# schematic.net
KiCad netlist of a schematic drawn in EAGLE
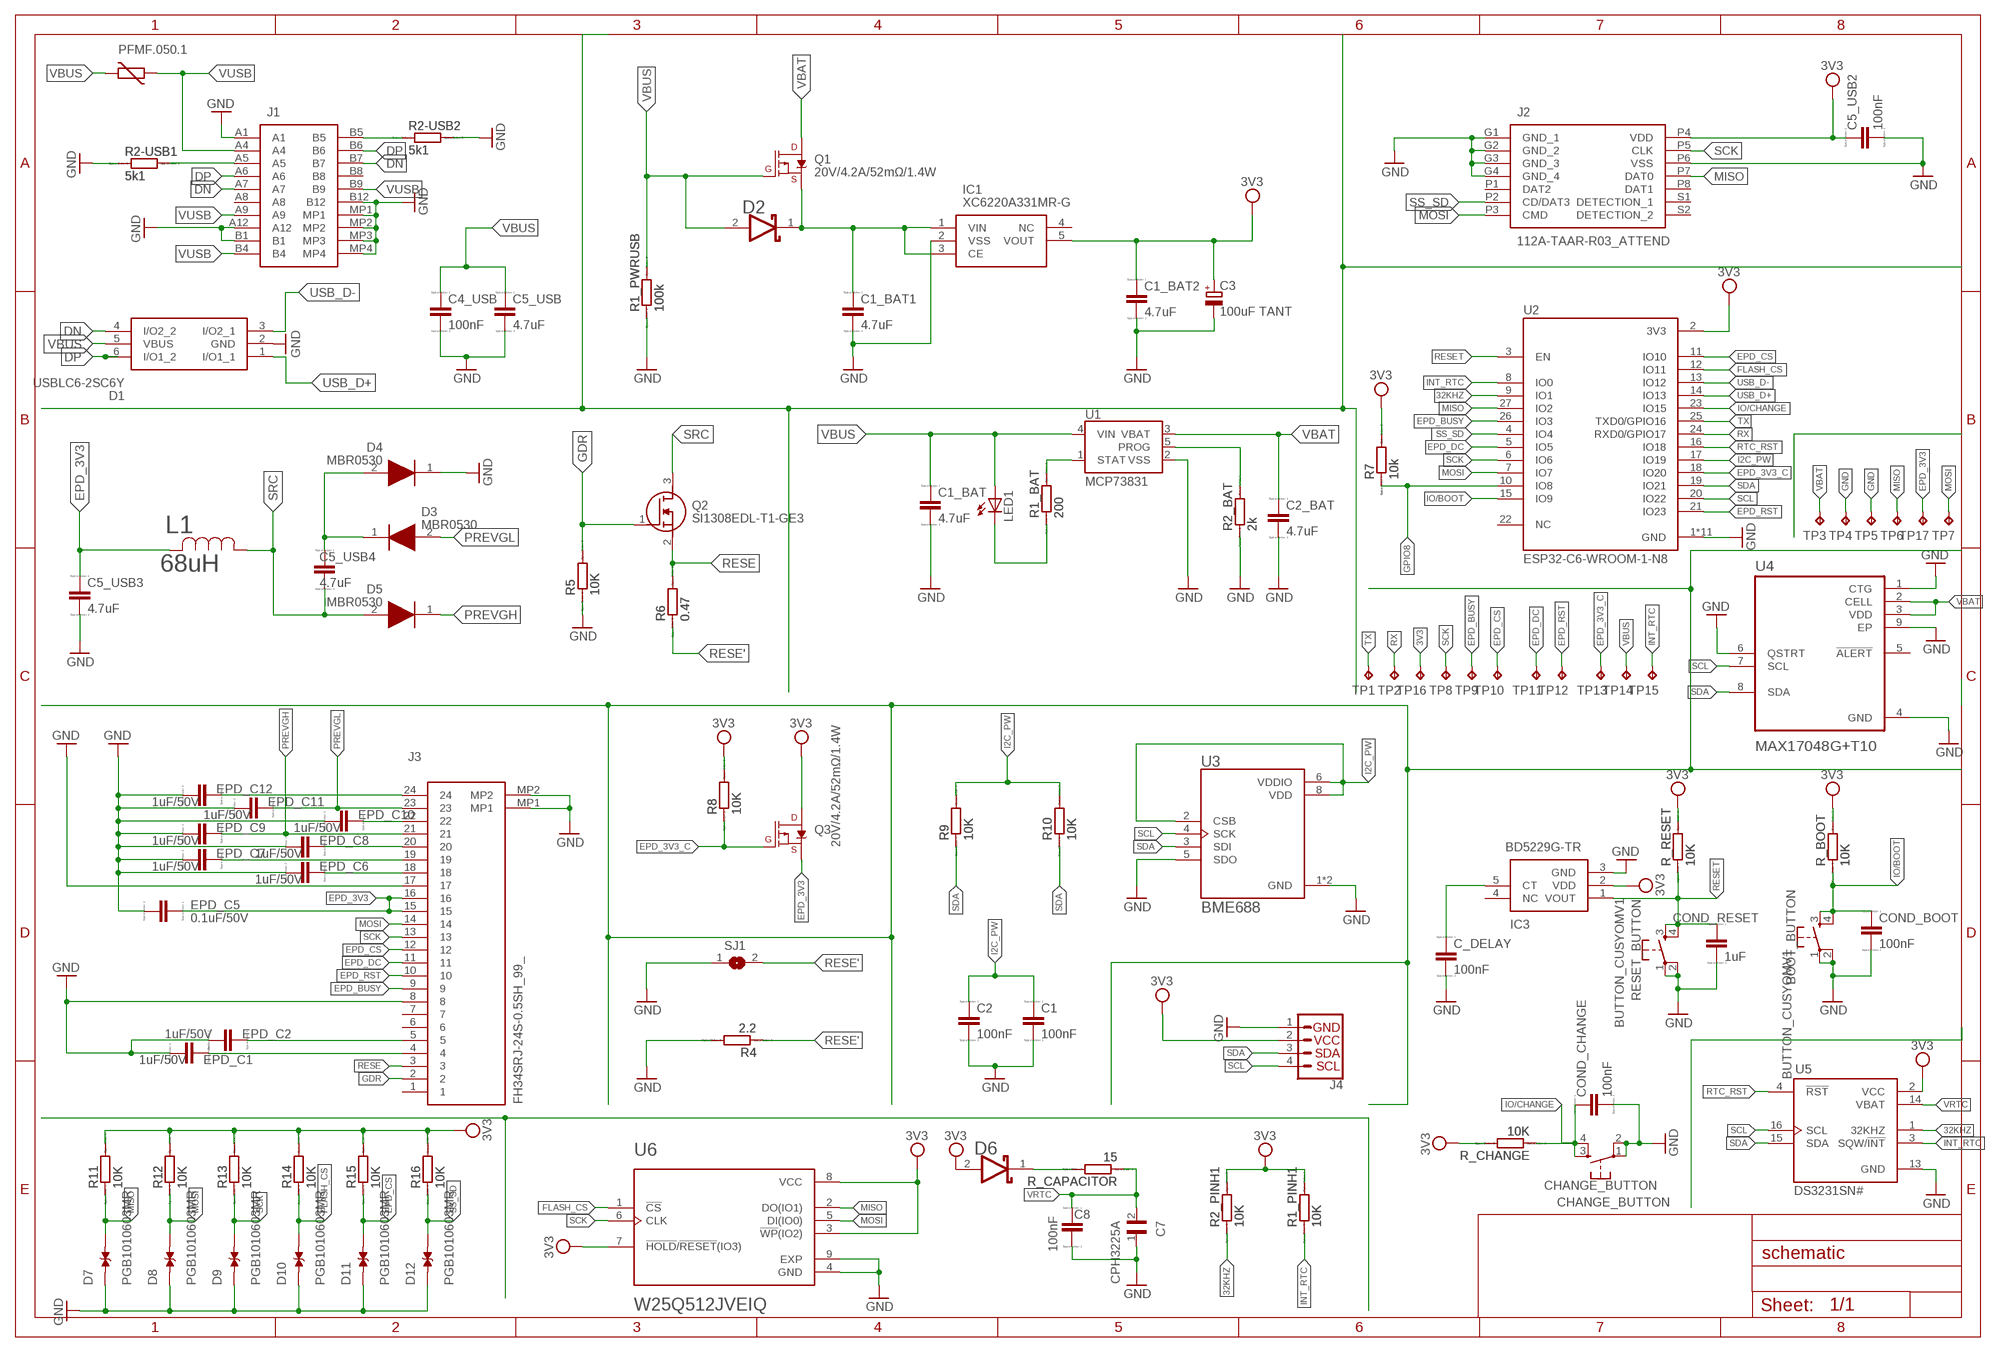
[diagram p0: schematic, sheet 1]

(export (version "E")
  (design (tool "Eeschema 10.0.6"))
  (components
    (comp (ref "BOOT_BUTTON")
      (value "BUTTON_CUSYOMV1")
      (footprint "eagle-import:MYBUTTON")
      (libsource (lib "eagle-import") (part "BUTTON_CUSYOMV1"))
    )
    (comp (ref "C1")
      (value "100nF")
      (footprint "eagle-import:ESP32_WROVER_EAGLE-LTSPICE_C0402")
      (libsource (lib "eagle-import") (part "ESP32_WROVER_EAGLE-LTSPICE_CC0402"))
    )
    (comp (ref "C1_BAT")
      (value "4.7uF")
      (footprint "eagle-import:ESP32_WROVER_EAGLE-LTSPICE_C0402")
      (libsource (lib "eagle-import") (part "ESP32_WROVER_EAGLE-LTSPICE_CC0402"))
    )
    (comp (ref "C1_BAT1")
      (value "4.7uF")
      (footprint "eagle-import:ESP32_WROVER_EAGLE-LTSPICE_C0402")
      (libsource (lib "eagle-import") (part "ESP32_WROVER_EAGLE-LTSPICE_CC0402"))
    )
    (comp (ref "C1_BAT2")
      (value "4.7uF")
      (footprint "eagle-import:ESP32_WROVER_EAGLE-LTSPICE_C0402")
      (libsource (lib "eagle-import") (part "ESP32_WROVER_EAGLE-LTSPICE_CC0402"))
    )
    (comp (ref "C2")
      (value "100nF")
      (footprint "eagle-import:ESP32_WROVER_EAGLE-LTSPICE_C0402")
      (libsource (lib "eagle-import") (part "ESP32_WROVER_EAGLE-LTSPICE_CC0402"))
    )
    (comp (ref "C2_BAT")
      (value "4.7uF")
      (footprint "eagle-import:ESP32_WROVER_EAGLE-LTSPICE_C0402")
      (libsource (lib "eagle-import") (part "ESP32_WROVER_EAGLE-LTSPICE_CC0402"))
    )
    (comp (ref "C3")
      (value "100uF TANT")
      (footprint "eagle-import:RCL_CT3528")
      (libsource (lib "eagle-import") (part "RCL_CPOL-EUCT3528"))
    )
    (comp (ref "C4_USB")
      (value "100nF")
      (footprint "eagle-import:ESP32_WROVER_EAGLE-LTSPICE_C0402")
      (libsource (lib "eagle-import") (part "ESP32_WROVER_EAGLE-LTSPICE_CC0402"))
    )
    (comp (ref "C5_USB")
      (value "4.7uF")
      (footprint "eagle-import:ESP32_WROVER_EAGLE-LTSPICE_C0402")
      (libsource (lib "eagle-import") (part "ESP32_WROVER_EAGLE-LTSPICE_CC0402"))
    )
    (comp (ref "C5_USB2")
      (value "100nF")
      (footprint "eagle-import:ESP32_WROVER_EAGLE-LTSPICE_C0402")
      (libsource (lib "eagle-import") (part "ESP32_WROVER_EAGLE-LTSPICE_CC0402"))
    )
    (comp (ref "C5_USB3")
      (value "4.7uF")
      (footprint "eagle-import:ESP32_WROVER_EAGLE-LTSPICE_C0402")
      (libsource (lib "eagle-import") (part "ESP32_WROVER_EAGLE-LTSPICE_CC0402"))
    )
    (comp (ref "C5_USB4")
      (value "4.7uF")
      (footprint "eagle-import:ESP32_WROVER_EAGLE-LTSPICE_C0402")
      (libsource (lib "eagle-import") (part "ESP32_WROVER_EAGLE-LTSPICE_CC0402"))
    )
    (comp (ref "C7")
      (value "CPH3225A")
      (footprint "eagle-import:CAPCP3225X100N")
      (fields (field (name "MF") "Seiko Instruments"))
      (libsource (lib "eagle-import") (part "CPH3225A"))
    )
    (comp (ref "C8")
      (value "100nF")
      (footprint "eagle-import:ESP32_WROVER_EAGLE-LTSPICE_C0402")
      (libsource (lib "eagle-import") (part "ESP32_WROVER_EAGLE-LTSPICE_CC0402"))
    )
    (comp (ref "CHANGE_BUTTON")
      (value "CHANGE_BUTTON")
      (footprint "eagle-import:MYBUTTON")
      (libsource (lib "eagle-import") (part "BUTTON_CUSYOMV1"))
    )
    (comp (ref "COND_BOOT")
      (value "100nF")
      (footprint "eagle-import:ESP32_WROVER_EAGLE-LTSPICE_C0402")
      (libsource (lib "eagle-import") (part "ESP32_WROVER_EAGLE-LTSPICE_CC0402"))
    )
    (comp (ref "COND_CHANGE")
      (value "100nF")
      (footprint "eagle-import:ESP32_WROVER_EAGLE-LTSPICE_C0402")
      (libsource (lib "eagle-import") (part "ESP32_WROVER_EAGLE-LTSPICE_CC0402"))
    )
    (comp (ref "COND_RESET")
      (value "1uF")
      (footprint "eagle-import:ESP32_WROVER_EAGLE-LTSPICE_C0402")
      (libsource (lib "eagle-import") (part "ESP32_WROVER_EAGLE-LTSPICE_CC0402"))
    )
    (comp (ref "C_DELAY")
      (value "100nF")
      (footprint "eagle-import:ESP32_WROVER_EAGLE-LTSPICE_C0402")
      (libsource (lib "eagle-import") (part "ESP32_WROVER_EAGLE-LTSPICE_CC0402"))
    )
    (comp (ref "D1")
      (value "USBLC6-2SC6Y")
      (footprint "eagle-import:SOT95P280X145-6N")
      (fields (field (name "MF") "STMicroelectronics"))
      (libsource (lib "eagle-import") (part "USBLC6-2SC6Y"))
    )
    (comp (ref "D2")
      (value "SD0805S020S1R0")
      (footprint "eagle-import:ESP32_WROVER_AVX---SD0805S020S1R0_AVX_SD0805S020S1R0_0")
      (fields
        (field (name "DIGIKEY_PART_NUMBER") "478-7800-1-ND")
        (field (name "MF") "AVX")
        (field (name "MOUSER_PART_NUMBER") "581-SD0805S020S1R0")
      )
      (libsource (lib "eagle-import") (part "ESP32_WROVER_AVX---SD0805S020S1R0_AVX_SD0805S020S1R0_0_0AVX_SD0805S020S1R0_0_0"))
    )
    (comp (ref "D3")
      (value "MBR0530")
      (footprint "eagle-import:SOD3716X135N")
      (fields (field (name "MF") "ON Semiconductor"))
      (libsource (lib "eagle-import") (part "MBR0530"))
    )
    (comp (ref "D4")
      (value "MBR0530")
      (footprint "eagle-import:SOD3716X135N")
      (fields (field (name "MF") "ON Semiconductor"))
      (libsource (lib "eagle-import") (part "MBR0530"))
    )
    (comp (ref "D5")
      (value "MBR0530")
      (footprint "eagle-import:SOD3716X135N")
      (fields (field (name "MF") "ON Semiconductor"))
      (libsource (lib "eagle-import") (part "MBR0530"))
    )
    (comp (ref "D6")
      (value "ESP32_WROVER_AVX---SD0805S020S1R0_AVX_SD0805S020S1R0_0_0AVX_SD0805S020S1R0_0_0")
      (footprint "eagle-import:ESP32_WROVER_AVX---SD0805S020S1R0_AVX_SD0805S020S1R0_0")
      (fields
        (field (name "DIGIKEY_PART_NUMBER") "478-7800-1-ND")
        (field (name "MF") "AVX")
        (field (name "MOUSER_PART_NUMBER") "581-SD0805S020S1R0")
      )
      (libsource (lib "eagle-import") (part "ESP32_WROVER_AVX---SD0805S020S1R0_AVX_SD0805S020S1R0_0_0AVX_SD0805S020S1R0_0_0"))
    )
    (comp (ref "D7")
      (value "PGB1010603MR")
      (footprint "eagle-import:DIOC1608X36N")
      (fields (field (name "MF") "Littelfuse Inc."))
      (libsource (lib "eagle-import") (part "PGB1010603MR"))
    )
    (comp (ref "D8")
      (value "PGB1010603MR")
      (footprint "eagle-import:DIOC1608X36N")
      (fields (field (name "MF") "Littelfuse Inc."))
      (libsource (lib "eagle-import") (part "PGB1010603MR"))
    )
    (comp (ref "D9")
      (value "PGB1010603MR")
      (footprint "eagle-import:DIOC1608X36N")
      (fields (field (name "MF") "Littelfuse Inc."))
      (libsource (lib "eagle-import") (part "PGB1010603MR"))
    )
    (comp (ref "D10")
      (value "PGB1010603MR")
      (footprint "eagle-import:DIOC1608X36N")
      (fields (field (name "MF") "Littelfuse Inc."))
      (libsource (lib "eagle-import") (part "PGB1010603MR"))
    )
    (comp (ref "D11")
      (value "PGB1010603MR")
      (footprint "eagle-import:DIOC1608X36N")
      (fields (field (name "MF") "Littelfuse Inc."))
      (libsource (lib "eagle-import") (part "PGB1010603MR"))
    )
    (comp (ref "D12")
      (value "PGB1010603MR")
      (footprint "eagle-import:DIOC1608X36N")
      (fields (field (name "MF") "Littelfuse Inc."))
      (libsource (lib "eagle-import") (part "PGB1010603MR"))
    )
    (comp (ref "EPD_C1")
      (value "1uF/50V")
      (footprint "eagle-import:ESP32_WROVER_EAGLE-LTSPICE_C0402")
      (libsource (lib "eagle-import") (part "ESP32_WROVER_EAGLE-LTSPICE_CC0402"))
    )
    (comp (ref "EPD_C2")
      (value "1uF/50V")
      (footprint "eagle-import:ESP32_WROVER_EAGLE-LTSPICE_C0402")
      (libsource (lib "eagle-import") (part "ESP32_WROVER_EAGLE-LTSPICE_CC0402"))
    )
    (comp (ref "EPD_C5")
      (value "0.1uF/50V")
      (footprint "eagle-import:ESP32_WROVER_EAGLE-LTSPICE_C0402")
      (libsource (lib "eagle-import") (part "ESP32_WROVER_EAGLE-LTSPICE_CC0402"))
    )
    (comp (ref "EPD_C6")
      (value "1uF/50V")
      (footprint "eagle-import:ESP32_WROVER_EAGLE-LTSPICE_C0402")
      (libsource (lib "eagle-import") (part "ESP32_WROVER_EAGLE-LTSPICE_CC0402"))
    )
    (comp (ref "EPD_C7")
      (value "1uF/50V")
      (footprint "eagle-import:ESP32_WROVER_EAGLE-LTSPICE_C0402")
      (libsource (lib "eagle-import") (part "ESP32_WROVER_EAGLE-LTSPICE_CC0402"))
    )
    (comp (ref "EPD_C8")
      (value "1uF/50V")
      (footprint "eagle-import:ESP32_WROVER_EAGLE-LTSPICE_C0402")
      (libsource (lib "eagle-import") (part "ESP32_WROVER_EAGLE-LTSPICE_CC0402"))
    )
    (comp (ref "EPD_C9")
      (value "1uF/50V")
      (footprint "eagle-import:ESP32_WROVER_EAGLE-LTSPICE_C0402")
      (libsource (lib "eagle-import") (part "ESP32_WROVER_EAGLE-LTSPICE_CC0402"))
    )
    (comp (ref "EPD_C10")
      (value "1uF/50V")
      (footprint "eagle-import:ESP32_WROVER_EAGLE-LTSPICE_C0402")
      (libsource (lib "eagle-import") (part "ESP32_WROVER_EAGLE-LTSPICE_CC0402"))
    )
    (comp (ref "EPD_C11")
      (value "1uF/50V")
      (footprint "eagle-import:ESP32_WROVER_EAGLE-LTSPICE_C0402")
      (libsource (lib "eagle-import") (part "ESP32_WROVER_EAGLE-LTSPICE_CC0402"))
    )
    (comp (ref "EPD_C12")
      (value "1uF/50V")
      (footprint "eagle-import:ESP32_WROVER_EAGLE-LTSPICE_C0402")
      (libsource (lib "eagle-import") (part "ESP32_WROVER_EAGLE-LTSPICE_CC0402"))
    )
    (comp (ref "IC1")
      (value "XC6220A331MR-G")
      (footprint "eagle-import:SOT95P280X120-5N")
      (libsource (lib "eagle-import") (part "XC6220A331MR-G"))
    )
    (comp (ref "IC3")
      (value "BD5229G-TR")
      (footprint "eagle-import:SOT95P280X125-5N")
      (fields (field (name "MOUSER_PART_NUMBER") "755-BD5229G-TR"))
      (libsource (lib "eagle-import") (part "BD5229G-TR"))
    )
    (comp (ref "J1")
      (value "SAMACSYS_PARTS_USB4110-GF-A")
      (footprint "eagle-import:SAMACSYS_PARTS_USB4110GFA")
      (fields
        (field (name "MANUFACTURER_PART_NUMBER") "USB4110-GF-A")
        (field (name "MOUSER_PART_NUMBER") "640-USB4110-GF-A")
      )
      (libsource (lib "eagle-import") (part "SAMACSYS_PARTS_USB4110-GF-A"))
    )
    (comp (ref "J2")
      (value "112A-TAAR-R03_ATTEND")
      (footprint "eagle-import:112ATAARR03ATTEND")
      (fields (field (name "MANUFACTURER_PART_NUMBER") "112A-TAAR-R03 ATTEND"))
      (libsource (lib "eagle-import") (part "112A-TAAR-R03_ATTEND"))
    )
    (comp (ref "J3")
      (value "FH34SRJ-24S-0.5SH_99_")
      (footprint "eagle-import:FH34SRJ24S05SH99")
      (fields
        (field (name "MANUFACTURER_PART_NUMBER") "FH34SRJ-24S-0.5SH(99)")
        (field (name "MOUSER_PART_NUMBER") "798-FH34SRJ24S05SH99")
      )
      (libsource (lib "eagle-import") (part "FH34SRJ-24S-0.5SH_99_"))
    )
    (comp (ref "J4")
      (value "QWIIC_RIGHT_ANGLE")
      (footprint "eagle-import:JST04_1MM_RA")
      (libsource (lib "eagle-import") (part "QWIIC_CONNECTOR"))
    )
    (comp (ref "L1")
      (value "68uH")
      (footprint "eagle-import:IND_4828-WE-TPC_WRE")
      (fields
        (field (name "MANUFACTURER_PART_NUMBER") "744043680")
        (field (name "COPYRIGHT") "Copyright (C) 2024 Ultra Librarian. All rights reserved.")
      )
      (libsource (lib "eagle-import") (part "744043680IND_4828-WE-TPC_WRE"))
    )
    (comp (ref "LED1")
      (value "ADAFRUIT_LEDCHIP-LED0603")
      (footprint "eagle-import:ADAFRUIT_CHIP-LED0603")
      (libsource (lib "eagle-import") (part "ADAFRUIT_LEDCHIP-LED0603"))
    )
    (comp (ref "PFMF.050.1")
      (value "ESP32C6_VARISTORCN1812")
      (footprint "eagle-import:ESP32C6_VARISTOR_CT_CN1812")
      (libsource (lib "eagle-import") (part "ESP32C6_VARISTORCN1812"))
    )
    (comp (ref "Q1")
      (value "20V/4.2A/52mΩ/1.4W")
      (footprint "eagle-import:ESP32_WROVER_SPARKFUN-DISCRETESEMI_SOT23-3")
      (libsource (lib "eagle-import") (part "ESP32_WROVER_SPARKFUN-DISCRETESEMI_MOSFET_PCH-DMG2305UX-7"))
    )
    (comp (ref "Q2")
      (value "SI1308EDL-T1-GE3")
      (footprint "eagle-import:SOT65P210X110-3N")
      (fields (field (name "MF") "Vishay Siliconix"))
      (libsource (lib "eagle-import") (part "SI1308EDL-T1-GE3"))
    )
    (comp (ref "Q3")
      (value "20V/4.2A/52mΩ/1.4W")
      (footprint "eagle-import:ESP32_WROVER_SPARKFUN-DISCRETESEMI_SOT23-3")
      (libsource (lib "eagle-import") (part "ESP32_WROVER_SPARKFUN-DISCRETESEMI_MOSFET_PCH-DMG2305UX-7"))
    )
    (comp (ref "R1_BAT")
      (value "200")
      (footprint "eagle-import:ESP32_WROVER_EAGLE-LTSPICE_R0402")
      (libsource (lib "eagle-import") (part "ESP32_WROVER_EAGLE-LTSPICE_RR0402"))
    )
    (comp (ref "R1_PINH1")
      (value "10K")
      (footprint "eagle-import:ESP32_WROVER_EAGLE-LTSPICE_R0402")
      (libsource (lib "eagle-import") (part "ESP32_WROVER_EAGLE-LTSPICE_RR0402"))
    )
    (comp (ref "R1_PWRUSB")
      (value "100k")
      (footprint "eagle-import:ESP32_WROVER_EAGLE-LTSPICE_R0402")
      (libsource (lib "eagle-import") (part "ESP32_WROVER_EAGLE-LTSPICE_RR0402"))
    )
    (comp (ref "R2-USB1")
      (value "5k1")
      (footprint "eagle-import:ESP32_WROVER_EAGLE-LTSPICE_R0402")
      (libsource (lib "eagle-import") (part "ESP32_WROVER_EAGLE-LTSPICE_RR0402"))
    )
    (comp (ref "R2-USB2")
      (value "5k1")
      (footprint "eagle-import:ESP32_WROVER_EAGLE-LTSPICE_R0402")
      (libsource (lib "eagle-import") (part "ESP32_WROVER_EAGLE-LTSPICE_RR0402"))
    )
    (comp (ref "R2_BAT")
      (value "2k")
      (footprint "eagle-import:ESP32_WROVER_EAGLE-LTSPICE_R0402")
      (libsource (lib "eagle-import") (part "ESP32_WROVER_EAGLE-LTSPICE_RR0402"))
    )
    (comp (ref "R2_PINH1")
      (value "10K")
      (footprint "eagle-import:ESP32_WROVER_EAGLE-LTSPICE_R0402")
      (libsource (lib "eagle-import") (part "ESP32_WROVER_EAGLE-LTSPICE_RR0402"))
    )
    (comp (ref "R4")
      (value "2.2")
      (footprint "eagle-import:ESP32_WROVER_EAGLE-LTSPICE_R0402")
      (libsource (lib "eagle-import") (part "ESP32_WROVER_EAGLE-LTSPICE_RR0402"))
    )
    (comp (ref "R5")
      (value "10K")
      (footprint "eagle-import:ESP32_WROVER_EAGLE-LTSPICE_R0402")
      (libsource (lib "eagle-import") (part "ESP32_WROVER_EAGLE-LTSPICE_RR0402"))
    )
    (comp (ref "R6")
      (value "0.47")
      (footprint "eagle-import:ESP32_WROVER_EAGLE-LTSPICE_R0402")
      (libsource (lib "eagle-import") (part "ESP32_WROVER_EAGLE-LTSPICE_RR0402"))
    )
    (comp (ref "R7")
      (value "10k")
      (footprint "eagle-import:ESP32_WROVER_EAGLE-LTSPICE_R0402")
      (libsource (lib "eagle-import") (part "ESP32_WROVER_EAGLE-LTSPICE_RR0402"))
    )
    (comp (ref "R8")
      (value "10K")
      (footprint "eagle-import:ESP32_WROVER_EAGLE-LTSPICE_R0402")
      (libsource (lib "eagle-import") (part "ESP32_WROVER_EAGLE-LTSPICE_RR0402"))
    )
    (comp (ref "R9")
      (value "10K")
      (footprint "eagle-import:ESP32_WROVER_EAGLE-LTSPICE_R0402")
      (libsource (lib "eagle-import") (part "ESP32_WROVER_EAGLE-LTSPICE_RR0402"))
    )
    (comp (ref "R10")
      (value "10K")
      (footprint "eagle-import:ESP32_WROVER_EAGLE-LTSPICE_R0402")
      (libsource (lib "eagle-import") (part "ESP32_WROVER_EAGLE-LTSPICE_RR0402"))
    )
    (comp (ref "R11")
      (value "10K")
      (footprint "eagle-import:ESP32_WROVER_EAGLE-LTSPICE_R0402")
      (libsource (lib "eagle-import") (part "ESP32_WROVER_EAGLE-LTSPICE_RR0402"))
    )
    (comp (ref "R12")
      (value "10K")
      (footprint "eagle-import:ESP32_WROVER_EAGLE-LTSPICE_R0402")
      (libsource (lib "eagle-import") (part "ESP32_WROVER_EAGLE-LTSPICE_RR0402"))
    )
    (comp (ref "R13")
      (value "10K")
      (footprint "eagle-import:ESP32_WROVER_EAGLE-LTSPICE_R0402")
      (libsource (lib "eagle-import") (part "ESP32_WROVER_EAGLE-LTSPICE_RR0402"))
    )
    (comp (ref "R14")
      (value "10K")
      (footprint "eagle-import:ESP32_WROVER_EAGLE-LTSPICE_R0402")
      (libsource (lib "eagle-import") (part "ESP32_WROVER_EAGLE-LTSPICE_RR0402"))
    )
    (comp (ref "R15")
      (value "10K")
      (footprint "eagle-import:ESP32_WROVER_EAGLE-LTSPICE_R0402")
      (libsource (lib "eagle-import") (part "ESP32_WROVER_EAGLE-LTSPICE_RR0402"))
    )
    (comp (ref "R16")
      (value "10K")
      (footprint "eagle-import:ESP32_WROVER_EAGLE-LTSPICE_R0402")
      (libsource (lib "eagle-import") (part "ESP32_WROVER_EAGLE-LTSPICE_RR0402"))
    )
    (comp (ref "RESET_BUTTON")
      (value "BUTTON_CUSYOMV1")
      (footprint "eagle-import:MYBUTTON")
      (libsource (lib "eagle-import") (part "BUTTON_CUSYOMV1"))
    )
    (comp (ref "R_BOOT")
      (value "10K")
      (footprint "eagle-import:ESP32_WROVER_EAGLE-LTSPICE_R0402")
      (libsource (lib "eagle-import") (part "ESP32_WROVER_EAGLE-LTSPICE_RR0402"))
    )
    (comp (ref "R_CAPACITOR")
      (value "15")
      (footprint "eagle-import:ESP32_WROVER_EAGLE-LTSPICE_R0402")
      (libsource (lib "eagle-import") (part "ESP32_WROVER_EAGLE-LTSPICE_RR0402"))
    )
    (comp (ref "R_CHANGE")
      (value "10K")
      (footprint "eagle-import:ESP32_WROVER_EAGLE-LTSPICE_R0402")
      (libsource (lib "eagle-import") (part "ESP32_WROVER_EAGLE-LTSPICE_RR0402"))
    )
    (comp (ref "R_RESET")
      (value "10K")
      (footprint "eagle-import:ESP32_WROVER_EAGLE-LTSPICE_R0402")
      (libsource (lib "eagle-import") (part "ESP32_WROVER_EAGLE-LTSPICE_RR0402"))
    )
    (comp (ref "SJ1") (value "SJ") (footprint "eagle-import:SJ") (libsource (lib "eagle-import") (part "SJ")))
    (comp (ref "TP1")
      (value "TPTP20R")
      (footprint "eagle-import:TP20R")
      (libsource (lib "eagle-import") (part "TPTP20R"))
    )
    (comp (ref "TP2")
      (value "TPTP20R")
      (footprint "eagle-import:TP20R")
      (libsource (lib "eagle-import") (part "TPTP20R"))
    )
    (comp (ref "TP3")
      (value "TPTP20R")
      (footprint "eagle-import:TP20R")
      (libsource (lib "eagle-import") (part "TPTP20R"))
    )
    (comp (ref "TP4")
      (value "TPTP20R")
      (footprint "eagle-import:TP20R")
      (libsource (lib "eagle-import") (part "TPTP20R"))
    )
    (comp (ref "TP5")
      (value "TPTP20R")
      (footprint "eagle-import:TP20R")
      (libsource (lib "eagle-import") (part "TPTP20R"))
    )
    (comp (ref "TP6")
      (value "TPTP20R")
      (footprint "eagle-import:TP20R")
      (libsource (lib "eagle-import") (part "TPTP20R"))
    )
    (comp (ref "TP7")
      (value "TPTP20R")
      (footprint "eagle-import:TP20R")
      (libsource (lib "eagle-import") (part "TPTP20R"))
    )
    (comp (ref "TP8")
      (value "TPTP20R")
      (footprint "eagle-import:TP20R")
      (libsource (lib "eagle-import") (part "TPTP20R"))
    )
    (comp (ref "TP9")
      (value "TPTP20R")
      (footprint "eagle-import:TP20R")
      (libsource (lib "eagle-import") (part "TPTP20R"))
    )
    (comp (ref "TP10")
      (value "TPTP20R")
      (footprint "eagle-import:TP20R")
      (libsource (lib "eagle-import") (part "TPTP20R"))
    )
    (comp (ref "TP11")
      (value "TPTP20R")
      (footprint "eagle-import:TP20R")
      (libsource (lib "eagle-import") (part "TPTP20R"))
    )
    (comp (ref "TP12")
      (value "TPTP20R")
      (footprint "eagle-import:TP20R")
      (libsource (lib "eagle-import") (part "TPTP20R"))
    )
    (comp (ref "TP13")
      (value "TPTP20R")
      (footprint "eagle-import:TP20R")
      (libsource (lib "eagle-import") (part "TPTP20R"))
    )
    (comp (ref "TP14")
      (value "TPTP20R")
      (footprint "eagle-import:TP20R")
      (libsource (lib "eagle-import") (part "TPTP20R"))
    )
    (comp (ref "TP15")
      (value "TPTP20R")
      (footprint "eagle-import:TP20R")
      (libsource (lib "eagle-import") (part "TPTP20R"))
    )
    (comp (ref "TP16")
      (value "TPTP20R")
      (footprint "eagle-import:TP20R")
      (libsource (lib "eagle-import") (part "TPTP20R"))
    )
    (comp (ref "TP17")
      (value "TPTP20R")
      (footprint "eagle-import:TP20R")
      (libsource (lib "eagle-import") (part "TPTP20R"))
    )
    (comp (ref "U1")
      (value "MCP73831")
      (footprint "eagle-import:ESP32_WROVER_SPARKFUN-IC-POWER_SOT23-5")
      (libsource (lib "eagle-import") (part "ESP32_WROVER_SPARKFUN-IC-POWER_MCP73831"))
    )
    (comp (ref "U2")
      (value "ESP32-C6-WROOM-1-N8")
      (footprint "eagle-import:XCVR_ESP32-C6-WROOM-1-N8")
      (fields (field (name "MF") "Espressif Systems"))
      (libsource (lib "eagle-import") (part "ESP32-C6-WROOM-1-N8"))
    )
    (comp (ref "U3")
      (value "BME688")
      (footprint "eagle-import:ESP32_WROVER_BME680_PSON80P300X300X100-8N")
      (fields (field (name "MF") "Bosch Sensortec") (field (name "MP") "BME680"))
      (libsource (lib "eagle-import") (part "ESP32_WROVER_BME680_BME680"))
    )
    (comp (ref "U4")
      (value "MAX17048G+T10")
      (footprint "eagle-import:SON50P200X200X80-9N")
      (fields (field (name "MF") "Analog Devices"))
      (libsource (lib "eagle-import") (part "MAX17048G+T10"))
    )
    (comp (ref "U5")
      (value "DS3231SN#")
      (footprint "eagle-import:SOIC127P1032X265-16N")
      (fields (field (name "MF") "Analog Devices"))
      (libsource (lib "eagle-import") (part "DS3231SN#"))
    )
    (comp (ref "U6")
      (value "W25Q512JVEIQ")
      (footprint "eagle-import:SON127P600X800X80-9N")
      (fields (field (name "MF") "Winbond Electronics"))
      (libsource (lib "eagle-import") (part "W25Q512JVEIQ"))
    )
  )
  (nets
    (net (code "1") (name "3V3") (class "Default")
      (node (ref "C1_BAT2") (pin "1") (pinfunction "1_1") (pintype "passive"))
      (node (ref "C3") (pin "+") (pinfunction "+_+") (pintype "passive"))
      (node (ref "C5_USB2") (pin "1") (pinfunction "1_1") (pintype "passive"))
      (node (ref "D6") (pin "2") (pinfunction "ANODE_2") (pintype "bidirectional"))
      (node (ref "IC1") (pin "5") (pinfunction "VOUT_5") (pintype "bidirectional"))
      (node (ref "IC3") (pin "2") (pinfunction "VDD_2") (pintype "bidirectional"))
      (node (ref "J2") (pin "P4") (pinfunction "VDD_P4") (pintype "bidirectional"))
      (node (ref "J4") (pin "2") (pinfunction "2_2") (pintype "power_in"))
      (node (ref "Q3") (pin "3") (pinfunction "D_3") (pintype "bidirectional"))
      (node (ref "R11") (pin "2") (pinfunction "2_2") (pintype "passive"))
      (node (ref "R12") (pin "2") (pinfunction "2_2") (pintype "passive"))
      (node (ref "R13") (pin "2") (pinfunction "2_2") (pintype "passive"))
      (node (ref "R14") (pin "2") (pinfunction "2_2") (pintype "passive"))
      (node (ref "R15") (pin "2") (pinfunction "2_2") (pintype "passive"))
      (node (ref "R16") (pin "2") (pinfunction "2_2") (pintype "passive"))
      (node (ref "R1_PINH1") (pin "2") (pinfunction "2_2") (pintype "passive"))
      (node (ref "R2_PINH1") (pin "2") (pinfunction "2_2") (pintype "passive"))
      (node (ref "R7") (pin "2") (pinfunction "2_2") (pintype "passive"))
      (node (ref "R8") (pin "2") (pinfunction "2_2") (pintype "passive"))
      (node (ref "R_BOOT") (pin "2") (pinfunction "2_2") (pintype "passive"))
      (node (ref "R_CHANGE") (pin "2") (pinfunction "2_2") (pintype "passive"))
      (node (ref "R_RESET") (pin "2") (pinfunction "2_2") (pintype "passive"))
      (node (ref "TP16") (pin "TP") (pinfunction "TP_TP") (pintype "input"))
      (node (ref "U2") (pin "2") (pinfunction "3V3_2") (pintype "power_in"))
      (node (ref "U5") (pin "2") (pinfunction "VCC_2") (pintype "power_in"))
      (node (ref "U6") (pin "3") (pinfunction "~{WP}(IO2)_3") (pintype "bidirectional"))
      (node (ref "U6") (pin "7") (pinfunction "~{HOLD}/~{RESET}(IO3)_7") (pintype "bidirectional"))
      (node (ref "U6") (pin "8") (pinfunction "VCC_8") (pintype "power_in"))
    )
    (net (code "2") (name "32KHZ") (class "Default")
      (node (ref "R2_PINH1") (pin "1") (pinfunction "1_1") (pintype "passive"))
      (node (ref "U2") (pin "9") (pinfunction "IO1_9") (pintype "bidirectional"))
      (node (ref "U5") (pin "1") (pinfunction "32KHZ_1") (pintype "output"))
    )
    (net (code "3") (name "DN") (class "Default")
      (node (ref "D1") (pin "4") (pinfunction "I/O2_2_4") (pintype "bidirectional"))
      (node (ref "J1") (pin "A7") (pinfunction "A7_A7") (pintype "bidirectional"))
      (node (ref "J1") (pin "B7") (pinfunction "B7_B7") (pintype "bidirectional"))
    )
    (net (code "4") (name "DP") (class "Default")
      (node (ref "D1") (pin "6") (pinfunction "I/O1_2_6") (pintype "bidirectional"))
      (node (ref "J1") (pin "A6") (pinfunction "A6_A6") (pintype "bidirectional"))
      (node (ref "J1") (pin "B6") (pinfunction "B6_B6") (pintype "bidirectional"))
    )
    (net (code "5") (name "EPD_3V3") (class "Default")
      (node (ref "C5_USB3") (pin "1") (pinfunction "1_1") (pintype "passive"))
      (node (ref "EPD_C5") (pin "1") (pinfunction "1_1") (pintype "passive"))
      (node (ref "J3") (pin "15") (pinfunction "15_15") (pintype "bidirectional"))
      (node (ref "J3") (pin "16") (pinfunction "16_16") (pintype "bidirectional"))
      (node (ref "L1") (pin "2") (pinfunction "2_2") (pintype "passive"))
      (node (ref "Q3") (pin "2") (pinfunction "S_2") (pintype "bidirectional"))
      (node (ref "TP17") (pin "TP") (pinfunction "TP_TP") (pintype "input"))
    )
    (net (code "6") (name "EPD_3V3_C") (class "Default")
      (node (ref "Q3") (pin "1") (pinfunction "G_1") (pintype "bidirectional"))
      (node (ref "R8") (pin "1") (pinfunction "1_1") (pintype "passive"))
      (node (ref "TP13") (pin "TP") (pinfunction "TP_TP") (pintype "input"))
      (node (ref "U2") (pin "18") (pinfunction "IO20_18") (pintype "bidirectional"))
    )
    (net (code "7") (name "EPD_BUSY") (class "Default")
      (node (ref "J3") (pin "9") (pinfunction "9_9") (pintype "bidirectional"))
      (node (ref "TP9") (pin "TP") (pinfunction "TP_TP") (pintype "input"))
      (node (ref "U2") (pin "26") (pinfunction "IO3_26") (pintype "bidirectional"))
    )
    (net (code "8") (name "EPD_CS") (class "Default")
      (node (ref "D11") (pin "2") (pinfunction "2_2") (pintype "passive"))
      (node (ref "J3") (pin "12") (pinfunction "12_12") (pintype "bidirectional"))
      (node (ref "R15") (pin "1") (pinfunction "1_1") (pintype "passive"))
      (node (ref "TP10") (pin "TP") (pinfunction "TP_TP") (pintype "input"))
      (node (ref "U2") (pin "11") (pinfunction "IO10_11") (pintype "bidirectional"))
    )
    (net (code "9") (name "EPD_DC") (class "Default")
      (node (ref "J3") (pin "11") (pinfunction "11_11") (pintype "bidirectional"))
      (node (ref "TP11") (pin "TP") (pinfunction "TP_TP") (pintype "input"))
      (node (ref "U2") (pin "5") (pinfunction "IO5_5") (pintype "bidirectional"))
    )
    (net (code "10") (name "EPD_RST") (class "Default")
      (node (ref "J3") (pin "10") (pinfunction "10_10") (pintype "bidirectional"))
      (node (ref "TP12") (pin "TP") (pinfunction "TP_TP") (pintype "input"))
      (node (ref "U2") (pin "21") (pinfunction "IO23_21") (pintype "bidirectional"))
    )
    (net (code "11") (name "FLASH_CS") (class "Default")
      (node (ref "D10") (pin "2") (pinfunction "2_2") (pintype "passive"))
      (node (ref "R14") (pin "1") (pinfunction "1_1") (pintype "passive"))
      (node (ref "U2") (pin "12") (pinfunction "IO11_12") (pintype "bidirectional"))
      (node (ref "U6") (pin "1") (pinfunction "~{CS}_1") (pintype "input"))
    )
    (net (code "12") (name "GDR") (class "Default")
      (node (ref "J3") (pin "2") (pinfunction "2_2") (pintype "bidirectional"))
      (node (ref "Q2") (pin "1") (pinfunction "G_1") (pintype "bidirectional"))
      (node (ref "R5") (pin "2") (pinfunction "2_2") (pintype "passive"))
    )
    (net (code "13") (name "GND") (class "Default")
      (node (ref "BOOT_BUTTON") (pin "1") (pinfunction "1_1") (pintype "passive"))
      (node (ref "BOOT_BUTTON") (pin "2") (pinfunction "2_2") (pintype "passive"))
      (node (ref "C1") (pin "2") (pinfunction "2_2") (pintype "passive"))
      (node (ref "C1_BAT") (pin "2") (pinfunction "2_2") (pintype "passive"))
      (node (ref "C1_BAT1") (pin "2") (pinfunction "2_2") (pintype "passive"))
      (node (ref "C1_BAT2") (pin "2") (pinfunction "2_2") (pintype "passive"))
      (node (ref "C2") (pin "2") (pinfunction "2_2") (pintype "passive"))
      (node (ref "C2_BAT") (pin "2") (pinfunction "2_2") (pintype "passive"))
      (node (ref "C3") (pin "-") (pinfunction "-_-") (pintype "passive"))
      (node (ref "C4_USB") (pin "2") (pinfunction "2_2") (pintype "passive"))
      (node (ref "C5_USB") (pin "2") (pinfunction "2_2") (pintype "passive"))
      (node (ref "C5_USB2") (pin "2") (pinfunction "2_2") (pintype "passive"))
      (node (ref "C5_USB3") (pin "2") (pinfunction "2_2") (pintype "passive"))
      (node (ref "C7") (pin "1") (pinfunction "1_1") (pintype "passive"))
      (node (ref "C8") (pin "2") (pinfunction "2_2") (pintype "passive"))
      (node (ref "CHANGE_BUTTON") (pin "1") (pinfunction "1_1") (pintype "passive"))
      (node (ref "CHANGE_BUTTON") (pin "2") (pinfunction "2_2") (pintype "passive"))
      (node (ref "COND_BOOT") (pin "2") (pinfunction "2_2") (pintype "passive"))
      (node (ref "COND_CHANGE") (pin "2") (pinfunction "2_2") (pintype "passive"))
      (node (ref "COND_RESET") (pin "2") (pinfunction "2_2") (pintype "passive"))
      (node (ref "C_DELAY") (pin "2") (pinfunction "2_2") (pintype "passive"))
      (node (ref "D1") (pin "2") (pinfunction "GND_2") (pintype "bidirectional"))
      (node (ref "D10") (pin "1") (pinfunction "1_1") (pintype "passive"))
      (node (ref "D11") (pin "1") (pinfunction "1_1") (pintype "passive"))
      (node (ref "D12") (pin "1") (pinfunction "1_1") (pintype "passive"))
      (node (ref "D4") (pin "1") (pinfunction "K_1") (pintype "bidirectional"))
      (node (ref "D7") (pin "1") (pinfunction "1_1") (pintype "passive"))
      (node (ref "D8") (pin "1") (pinfunction "1_1") (pintype "passive"))
      (node (ref "D9") (pin "1") (pinfunction "1_1") (pintype "passive"))
      (node (ref "EPD_C1") (pin "2") (pinfunction "2_2") (pintype "passive"))
      (node (ref "EPD_C10") (pin "2") (pinfunction "2_2") (pintype "passive"))
      (node (ref "EPD_C11") (pin "2") (pinfunction "2_2") (pintype "passive"))
      (node (ref "EPD_C12") (pin "2") (pinfunction "2_2") (pintype "passive"))
      (node (ref "EPD_C2") (pin "2") (pinfunction "2_2") (pintype "passive"))
      (node (ref "EPD_C5") (pin "2") (pinfunction "2_2") (pintype "passive"))
      (node (ref "EPD_C6") (pin "2") (pinfunction "2_2") (pintype "passive"))
      (node (ref "EPD_C7") (pin "2") (pinfunction "2_2") (pintype "passive"))
      (node (ref "EPD_C8") (pin "2") (pinfunction "2_2") (pintype "passive"))
      (node (ref "EPD_C9") (pin "2") (pinfunction "2_2") (pintype "passive"))
      (node (ref "IC1") (pin "2") (pinfunction "VSS_2") (pintype "bidirectional"))
      (node (ref "IC3") (pin "3") (pinfunction "GND_3") (pintype "bidirectional"))
      (node (ref "J1") (pin "A1") (pinfunction "A1_A1") (pintype "bidirectional"))
      (node (ref "J1") (pin "A12") (pinfunction "A12_A12") (pintype "bidirectional"))
      (node (ref "J1") (pin "B1") (pinfunction "B1_B1") (pintype "bidirectional"))
      (node (ref "J1") (pin "B12") (pinfunction "B12_B12") (pintype "bidirectional"))
      (node (ref "J1") (pin "MP1") (pinfunction "MP1_MP1") (pintype "bidirectional"))
      (node (ref "J1") (pin "MP2") (pinfunction "MP2_MP2") (pintype "bidirectional"))
      (node (ref "J1") (pin "MP3") (pinfunction "MP3_MP3") (pintype "bidirectional"))
      (node (ref "J1") (pin "MP4") (pinfunction "MP4_MP4") (pintype "bidirectional"))
      (node (ref "J2") (pin "G1") (pinfunction "GND_1_G1") (pintype "bidirectional"))
      (node (ref "J2") (pin "G2") (pinfunction "GND_2_G2") (pintype "bidirectional"))
      (node (ref "J2") (pin "G3") (pinfunction "GND_3_G3") (pintype "bidirectional"))
      (node (ref "J2") (pin "G4") (pinfunction "GND_4_G4") (pintype "bidirectional"))
      (node (ref "J2") (pin "P6") (pinfunction "VSS_P6") (pintype "bidirectional"))
      (node (ref "J3") (pin "17") (pinfunction "17_17") (pintype "bidirectional"))
      (node (ref "J3") (pin "8") (pinfunction "8_8") (pintype "bidirectional"))
      (node (ref "J3") (pin "MP1") (pinfunction "MP1_MP1") (pintype "bidirectional"))
      (node (ref "J3") (pin "MP2") (pinfunction "MP2_MP2") (pintype "bidirectional"))
      (node (ref "J4") (pin "1") (pinfunction "1_1") (pintype "power_in"))
      (node (ref "R1_PWRUSB") (pin "1") (pinfunction "1_1") (pintype "passive"))
      (node (ref "R2-USB1") (pin "1") (pinfunction "1_1") (pintype "passive"))
      (node (ref "R2-USB2") (pin "2") (pinfunction "2_2") (pintype "passive"))
      (node (ref "R2_BAT") (pin "1") (pinfunction "1_1") (pintype "passive"))
      (node (ref "R4") (pin "2") (pinfunction "2_2") (pintype "passive"))
      (node (ref "R5") (pin "1") (pinfunction "1_1") (pintype "passive"))
      (node (ref "RESET_BUTTON") (pin "1") (pinfunction "1_1") (pintype "passive"))
      (node (ref "RESET_BUTTON") (pin "2") (pinfunction "2_2") (pintype "passive"))
      (node (ref "SJ1") (pin "1") (pinfunction "1_1") (pintype "passive"))
      (node (ref "TP4") (pin "TP") (pinfunction "TP_TP") (pintype "input"))
      (node (ref "TP5") (pin "TP") (pinfunction "TP_TP") (pintype "input"))
      (node (ref "U1") (pin "2") (pinfunction "VSS_2") (pintype "power_in"))
      (node (ref "U2") (pin "1") (pinfunction "GND_1") (pintype "power_in"))
      (node (ref "U2") (pin "28") (pinfunction "GND_28") (pintype "power_in"))
      (node (ref "U2") (pin "29_1") (pinfunction "GND_29_1") (pintype "power_in"))
      (node (ref "U2") (pin "29_2") (pinfunction "GND_29_2") (pintype "power_in"))
      (node (ref "U2") (pin "29_3") (pinfunction "GND_29_3") (pintype "power_in"))
      (node (ref "U2") (pin "29_4") (pinfunction "GND_29_4") (pintype "power_in"))
      (node (ref "U2") (pin "29_5") (pinfunction "GND_29_5") (pintype "power_in"))
      (node (ref "U2") (pin "29_6") (pinfunction "GND_29_6") (pintype "power_in"))
      (node (ref "U2") (pin "29_7") (pinfunction "GND_29_7") (pintype "power_in"))
      (node (ref "U2") (pin "29_8") (pinfunction "GND_29_8") (pintype "power_in"))
      (node (ref "U2") (pin "29_9") (pinfunction "GND_29_9") (pintype "power_in"))
      (node (ref "U3") (pin "1") (pinfunction "GND_1") (pintype "power_in"))
      (node (ref "U3") (pin "5") (pinfunction "SDO_5") (pintype "bidirectional"))
      (node (ref "U3") (pin "7") (pinfunction "GND_7") (pintype "power_in"))
      (node (ref "U4") (pin "1") (pinfunction "CTG_1") (pintype "power_in"))
      (node (ref "U4") (pin "4") (pinfunction "GND_4") (pintype "power_in"))
      (node (ref "U4") (pin "6") (pinfunction "QSTRT_6") (pintype "input"))
      (node (ref "U4") (pin "9") (pinfunction "EP_9") (pintype "power_in"))
      (node (ref "U5") (pin "13") (pinfunction "GND_13") (pintype "power_in"))
      (node (ref "U6") (pin "4") (pinfunction "GND_4") (pintype "power_in"))
      (node (ref "U6") (pin "9") (pinfunction "EXP_9") (pintype "passive"))
    )
    (net (code "14") (name "GPIO8") (class "Default")
      (node (ref "R7") (pin "1") (pinfunction "1_1") (pintype "passive"))
      (node (ref "U2") (pin "10") (pinfunction "IO8_10") (pintype "bidirectional"))
    )
    (net (code "15") (name "I2C_PW") (class "Default")
      (node (ref "C1") (pin "1") (pinfunction "1_1") (pintype "passive"))
      (node (ref "C2") (pin "1") (pinfunction "1_1") (pintype "passive"))
      (node (ref "R10") (pin "2") (pinfunction "2_2") (pintype "passive"))
      (node (ref "R9") (pin "2") (pinfunction "2_2") (pintype "passive"))
      (node (ref "U2") (pin "17") (pinfunction "IO19_17") (pintype "bidirectional"))
      (node (ref "U3") (pin "2") (pinfunction "CSB_2") (pintype "input"))
      (node (ref "U3") (pin "6") (pinfunction "VDDIO_6") (pintype "power_in"))
      (node (ref "U3") (pin "8") (pinfunction "VDD_8") (pintype "power_in"))
    )
    (net (code "16") (name "INT_RTC") (class "Default")
      (node (ref "R1_PINH1") (pin "1") (pinfunction "1_1") (pintype "passive"))
      (node (ref "TP15") (pin "TP") (pinfunction "TP_TP") (pintype "input"))
      (node (ref "U2") (pin "8") (pinfunction "IO0_8") (pintype "bidirectional"))
      (node (ref "U5") (pin "3") (pinfunction "SQW/~{INT}_3") (pintype "output"))
    )
    (net (code "17") (name "IO{slash}BOOT") (class "Default")
      (node (ref "BOOT_BUTTON") (pin "3") (pinfunction "3_3") (pintype "passive"))
      (node (ref "BOOT_BUTTON") (pin "4") (pinfunction "4_4") (pintype "passive"))
      (node (ref "COND_BOOT") (pin "1") (pinfunction "1_1") (pintype "passive"))
      (node (ref "R_BOOT") (pin "1") (pinfunction "1_1") (pintype "passive"))
      (node (ref "U2") (pin "15") (pinfunction "IO9_15") (pintype "bidirectional"))
    )
    (net (code "18") (name "IO{slash}CHANGE") (class "Default")
      (node (ref "CHANGE_BUTTON") (pin "3") (pinfunction "3_3") (pintype "passive"))
      (node (ref "CHANGE_BUTTON") (pin "4") (pinfunction "4_4") (pintype "passive"))
      (node (ref "COND_CHANGE") (pin "1") (pinfunction "1_1") (pintype "passive"))
      (node (ref "R_CHANGE") (pin "1") (pinfunction "1_1") (pintype "passive"))
      (node (ref "U2") (pin "23") (pinfunction "IO15_23") (pintype "bidirectional"))
    )
    (net (code "19") (name "MISO") (class "Default")
      (node (ref "D7") (pin "2") (pinfunction "2_2") (pintype "passive"))
      (node (ref "J2") (pin "P7") (pinfunction "DAT0_P7") (pintype "bidirectional"))
      (node (ref "R11") (pin "1") (pinfunction "1_1") (pintype "passive"))
      (node (ref "TP6") (pin "TP") (pinfunction "TP_TP") (pintype "input"))
      (node (ref "U2") (pin "27") (pinfunction "IO2_27") (pintype "bidirectional"))
      (node (ref "U6") (pin "2") (pinfunction "DO(IO1)_2") (pintype "bidirectional"))
    )
    (net (code "20") (name "MOSI") (class "Default")
      (node (ref "D8") (pin "2") (pinfunction "2_2") (pintype "passive"))
      (node (ref "J2") (pin "P3") (pinfunction "CMD_P3") (pintype "bidirectional"))
      (node (ref "J3") (pin "14") (pinfunction "14_14") (pintype "bidirectional"))
      (node (ref "R12") (pin "1") (pinfunction "1_1") (pintype "passive"))
      (node (ref "TP7") (pin "TP") (pinfunction "TP_TP") (pintype "input"))
      (node (ref "U2") (pin "7") (pinfunction "IO7_7") (pintype "bidirectional"))
      (node (ref "U6") (pin "5") (pinfunction "DI(IO0)_5") (pintype "bidirectional"))
    )
    (net (code "21") (name "Net-(D2-CATHODE)") (class "Default")
      (node (ref "C1_BAT1") (pin "1") (pinfunction "1_1") (pintype "passive"))
      (node (ref "D2") (pin "1") (pinfunction "CATHODE_1") (pintype "bidirectional"))
      (node (ref "IC1") (pin "1") (pinfunction "VIN_1") (pintype "bidirectional"))
      (node (ref "IC1") (pin "3") (pinfunction "CE_3") (pintype "bidirectional"))
      (node (ref "Q1") (pin "2") (pinfunction "S_2") (pintype "bidirectional"))
    )
    (net (code "22") (name "Net-(D3-K)") (class "Default")
      (node (ref "C5_USB4") (pin "1") (pinfunction "1_1") (pintype "passive"))
      (node (ref "D3") (pin "1") (pinfunction "K_1") (pintype "bidirectional"))
      (node (ref "D4") (pin "2") (pinfunction "A_2") (pintype "bidirectional"))
    )
    (net (code "23") (name "Net-(D6-CATHODE)") (class "Default")
      (node (ref "D6") (pin "1") (pinfunction "CATHODE_1") (pintype "bidirectional"))
      (node (ref "R_CAPACITOR") (pin "2") (pinfunction "2_2") (pintype "passive"))
    )
    (net (code "24") (name "Net-(EPD_C1-Pad1)") (class "Default")
      (node (ref "EPD_C1") (pin "1") (pinfunction "1_1") (pintype "passive"))
      (node (ref "J3") (pin "4") (pinfunction "4_4") (pintype "bidirectional"))
    )
    (net (code "25") (name "Net-(EPD_C2-Pad1)") (class "Default")
      (node (ref "EPD_C2") (pin "1") (pinfunction "1_1") (pintype "passive"))
      (node (ref "J3") (pin "5") (pinfunction "5_5") (pintype "bidirectional"))
    )
    (net (code "26") (name "Net-(EPD_C6-Pad1)") (class "Default")
      (node (ref "EPD_C6") (pin "1") (pinfunction "1_1") (pintype "passive"))
      (node (ref "J3") (pin "18") (pinfunction "18_18") (pintype "bidirectional"))
    )
    (net (code "27") (name "Net-(EPD_C7-Pad1)") (class "Default")
      (node (ref "EPD_C7") (pin "1") (pinfunction "1_1") (pintype "passive"))
      (node (ref "J3") (pin "19") (pinfunction "19_19") (pintype "bidirectional"))
    )
    (net (code "28") (name "Net-(EPD_C8-Pad1)") (class "Default")
      (node (ref "EPD_C8") (pin "1") (pinfunction "1_1") (pintype "passive"))
      (node (ref "J3") (pin "20") (pinfunction "20_20") (pintype "bidirectional"))
    )
    (net (code "29") (name "Net-(EPD_C10-Pad1)") (class "Default")
      (node (ref "EPD_C10") (pin "1") (pinfunction "1_1") (pintype "passive"))
      (node (ref "J3") (pin "22") (pinfunction "22_22") (pintype "bidirectional"))
    )
    (net (code "30") (name "Net-(EPD_C12-Pad1)") (class "Default")
      (node (ref "EPD_C12") (pin "1") (pinfunction "1_1") (pintype "passive"))
      (node (ref "J3") (pin "24") (pinfunction "24_24") (pintype "bidirectional"))
    )
    (net (code "31") (name "Net-(IC3-CT)") (class "Default")
      (node (ref "C_DELAY") (pin "1") (pinfunction "1_1") (pintype "passive"))
      (node (ref "IC3") (pin "5") (pinfunction "CT_5") (pintype "bidirectional"))
    )
    (net (code "32") (name "Net-(J1-PadA5)") (class "Default")
      (node (ref "J1") (pin "A5") (pinfunction "A5_A5") (pintype "bidirectional"))
      (node (ref "R2-USB1") (pin "2") (pinfunction "2_2") (pintype "passive"))
    )
    (net (code "33") (name "Net-(J1-PadB5)") (class "Default")
      (node (ref "J1") (pin "B5") (pinfunction "B5_B5") (pintype "bidirectional"))
      (node (ref "R2-USB2") (pin "1") (pinfunction "1_1") (pintype "passive"))
    )
    (net (code "34") (name "Net-(LED1-PadC)") (class "Default")
      (node (ref "LED1") (pin "C") (pinfunction "C_C") (pintype "passive"))
      (node (ref "R1_BAT") (pin "1") (pinfunction "1_1") (pintype "passive"))
    )
    (net (code "35") (name "Net-(U1-PROG)") (class "Default")
      (node (ref "R2_BAT") (pin "2") (pinfunction "2_2") (pintype "passive"))
      (node (ref "U1") (pin "5") (pinfunction "PROG_5") (pintype "input"))
    )
    (net (code "36") (name "Net-(U1-STAT)") (class "Default")
      (node (ref "R1_BAT") (pin "2") (pinfunction "2_2") (pintype "passive"))
      (node (ref "U1") (pin "1") (pinfunction "STAT_1") (pintype "output"))
    )
    (net (code "37") (name "PREVGH") (class "Default")
      (node (ref "D5") (pin "1") (pinfunction "K_1") (pintype "bidirectional"))
      (node (ref "EPD_C9") (pin "1") (pinfunction "1_1") (pintype "passive"))
      (node (ref "J3") (pin "21") (pinfunction "21_21") (pintype "bidirectional"))
    )
    (net (code "38") (name "PREVGL") (class "Default")
      (node (ref "D3") (pin "2") (pinfunction "A_2") (pintype "bidirectional"))
      (node (ref "EPD_C11") (pin "1") (pinfunction "1_1") (pintype "passive"))
      (node (ref "J3") (pin "23") (pinfunction "23_23") (pintype "bidirectional"))
    )
    (net (code "39") (name "RESE") (class "Default")
      (node (ref "J3") (pin "3") (pinfunction "3_3") (pintype "bidirectional"))
      (node (ref "Q2") (pin "2") (pinfunction "S_2") (pintype "bidirectional"))
      (node (ref "R6") (pin "2") (pinfunction "2_2") (pintype "passive"))
    )
    (net (code "40") (name "RESE'") (class "Default")
      (node (ref "R4") (pin "1") (pinfunction "1_1") (pintype "passive"))
      (node (ref "R6") (pin "1") (pinfunction "1_1") (pintype "passive"))
      (node (ref "SJ1") (pin "2") (pinfunction "2_2") (pintype "passive"))
    )
    (net (code "41") (name "RESET") (class "Default")
      (node (ref "COND_RESET") (pin "1") (pinfunction "1_1") (pintype "passive"))
      (node (ref "IC3") (pin "1") (pinfunction "VOUT_1") (pintype "bidirectional"))
      (node (ref "RESET_BUTTON") (pin "3") (pinfunction "3_3") (pintype "passive"))
      (node (ref "RESET_BUTTON") (pin "4") (pinfunction "4_4") (pintype "passive"))
      (node (ref "R_RESET") (pin "1") (pinfunction "1_1") (pintype "passive"))
      (node (ref "U2") (pin "3") (pinfunction "EN_3") (pintype "input"))
    )
    (net (code "42") (name "RTC_RST") (class "Default")
      (node (ref "U2") (pin "16") (pinfunction "IO18_16") (pintype "bidirectional"))
      (node (ref "U5") (pin "4") (pinfunction "~{RST}_4") (pintype "input"))
    )
    (net (code "43") (name "RX") (class "Default")
      (node (ref "TP2") (pin "TP") (pinfunction "TP_TP") (pintype "input"))
      (node (ref "U2") (pin "24") (pinfunction "RXD0/GPIO17_24") (pintype "bidirectional"))
    )
    (net (code "44") (name "SCK") (class "Default")
      (node (ref "D9") (pin "2") (pinfunction "2_2") (pintype "passive"))
      (node (ref "J2") (pin "P5") (pinfunction "CLK_P5") (pintype "bidirectional"))
      (node (ref "J3") (pin "13") (pinfunction "13_13") (pintype "bidirectional"))
      (node (ref "R13") (pin "1") (pinfunction "1_1") (pintype "passive"))
      (node (ref "TP8") (pin "TP") (pinfunction "TP_TP") (pintype "input"))
      (node (ref "U2") (pin "6") (pinfunction "IO6_6") (pintype "bidirectional"))
      (node (ref "U6") (pin "6") (pinfunction "CLK_6") (pintype "input"))
    )
    (net (code "45") (name "SCL") (class "Default")
      (node (ref "J4") (pin "4") (pinfunction "4_4") (pintype "passive"))
      (node (ref "U2") (pin "20") (pinfunction "IO22_20") (pintype "bidirectional"))
      (node (ref "U3") (pin "4") (pinfunction "SCK_4") (pintype "input"))
      (node (ref "U4") (pin "7") (pinfunction "SCL_7") (pintype "input"))
      (node (ref "U5") (pin "16") (pinfunction "SCL_16") (pintype "input"))
    )
    (net (code "46") (name "SDA") (class "Default")
      (node (ref "J4") (pin "3") (pinfunction "3_3") (pintype "passive"))
      (node (ref "R10") (pin "1") (pinfunction "1_1") (pintype "passive"))
      (node (ref "R9") (pin "1") (pinfunction "1_1") (pintype "passive"))
      (node (ref "U2") (pin "19") (pinfunction "IO21_19") (pintype "bidirectional"))
      (node (ref "U3") (pin "3") (pinfunction "SDI_3") (pintype "bidirectional"))
      (node (ref "U4") (pin "8") (pinfunction "SDA_8") (pintype "bidirectional"))
      (node (ref "U5") (pin "15") (pinfunction "SDA_15") (pintype "bidirectional"))
    )
    (net (code "47") (name "SRC") (class "Default")
      (node (ref "C5_USB4") (pin "2") (pinfunction "2_2") (pintype "passive"))
      (node (ref "D5") (pin "2") (pinfunction "A_2") (pintype "bidirectional"))
      (node (ref "L1") (pin "1") (pinfunction "1_1") (pintype "passive"))
      (node (ref "Q2") (pin "3") (pinfunction "D_3") (pintype "bidirectional"))
    )
    (net (code "48") (name "SS_SD") (class "Default")
      (node (ref "D12") (pin "2") (pinfunction "2_2") (pintype "passive"))
      (node (ref "J2") (pin "P2") (pinfunction "CD/DAT3_P2") (pintype "bidirectional"))
      (node (ref "R16") (pin "1") (pinfunction "1_1") (pintype "passive"))
      (node (ref "U2") (pin "4") (pinfunction "IO4_4") (pintype "bidirectional"))
    )
    (net (code "49") (name "TX") (class "Default")
      (node (ref "TP1") (pin "TP") (pinfunction "TP_TP") (pintype "input"))
      (node (ref "U2") (pin "25") (pinfunction "TXD0/GPIO16_25") (pintype "bidirectional"))
    )
    (net (code "50") (name "USB_D+") (class "Default")
      (node (ref "D1") (pin "1") (pinfunction "I/O1_1_1") (pintype "bidirectional"))
      (node (ref "U2") (pin "14") (pinfunction "IO13_14") (pintype "bidirectional"))
    )
    (net (code "51") (name "USB_D-") (class "Default")
      (node (ref "D1") (pin "3") (pinfunction "I/O2_1_3") (pintype "bidirectional"))
      (node (ref "U2") (pin "13") (pinfunction "IO12_13") (pintype "bidirectional"))
    )
    (net (code "52") (name "VBAT") (class "Default")
      (node (ref "C2_BAT") (pin "1") (pinfunction "1_1") (pintype "passive"))
      (node (ref "Q1") (pin "3") (pinfunction "D_3") (pintype "bidirectional"))
      (node (ref "TP3") (pin "TP") (pinfunction "TP_TP") (pintype "input"))
      (node (ref "U1") (pin "3") (pinfunction "VBAT_3") (pintype "power_in"))
      (node (ref "U4") (pin "2") (pinfunction "CELL_2") (pintype "power_in"))
      (node (ref "U4") (pin "3") (pinfunction "VDD_3") (pintype "power_in"))
    )
    (net (code "53") (name "VBUS") (class "Default")
      (node (ref "C1_BAT") (pin "1") (pinfunction "1_1") (pintype "passive"))
      (node (ref "C4_USB") (pin "1") (pinfunction "1_1") (pintype "passive"))
      (node (ref "C5_USB") (pin "1") (pinfunction "1_1") (pintype "passive"))
      (node (ref "D1") (pin "5") (pinfunction "VBUS_5") (pintype "bidirectional"))
      (node (ref "D2") (pin "2") (pinfunction "ANODE_2") (pintype "bidirectional"))
      (node (ref "LED1") (pin "A") (pinfunction "A_A") (pintype "passive"))
      (node (ref "PFMF.050.1") (pin "2") (pinfunction "2_2") (pintype "passive"))
      (node (ref "Q1") (pin "1") (pinfunction "G_1") (pintype "bidirectional"))
      (node (ref "R1_PWRUSB") (pin "2") (pinfunction "2_2") (pintype "passive"))
      (node (ref "TP14") (pin "TP") (pinfunction "TP_TP") (pintype "input"))
      (node (ref "U1") (pin "4") (pinfunction "VIN_4") (pintype "power_in"))
    )
    (net (code "54") (name "VRTC") (class "Default")
      (node (ref "C7") (pin "2") (pinfunction "2_2") (pintype "passive"))
      (node (ref "C8") (pin "1") (pinfunction "1_1") (pintype "passive"))
      (node (ref "R_CAPACITOR") (pin "1") (pinfunction "1_1") (pintype "passive"))
      (node (ref "U5") (pin "14") (pinfunction "VBAT_14") (pintype "power_in"))
    )
    (net (code "55") (name "VUSB") (class "Default")
      (node (ref "J1") (pin "A4") (pinfunction "A4_A4") (pintype "bidirectional"))
      (node (ref "J1") (pin "A9") (pinfunction "A9_A9") (pintype "bidirectional"))
      (node (ref "J1") (pin "B4") (pinfunction "B4_B4") (pintype "bidirectional"))
      (node (ref "J1") (pin "B9") (pinfunction "B9_B9") (pintype "bidirectional"))
      (node (ref "PFMF.050.1") (pin "1") (pinfunction "1_1") (pintype "passive"))
    )
    (net (code "56") (name "unconnected-(IC1-NC-Pad4)") (class "Default")
      (node (ref "IC1") (pin "4") (pinfunction "NC_4") (pintype "no_connect"))
    )
    (net (code "57") (name "unconnected-(IC3-NC-Pad4)") (class "Default")
      (node (ref "IC3") (pin "4") (pinfunction "NC_4") (pintype "no_connect"))
    )
    (net (code "58") (name "unconnected-(J1-PadA8)") (class "Default")
      (node (ref "J1") (pin "A8") (pinfunction "A8_A8") (pintype "bidirectional"))
    )
    (net (code "59") (name "unconnected-(J1-PadB8)") (class "Default")
      (node (ref "J1") (pin "B8") (pinfunction "B8_B8") (pintype "bidirectional"))
    )
    (net (code "60") (name "unconnected-(J2-DAT1-PadP8)") (class "Default")
      (node (ref "J2") (pin "P8") (pinfunction "DAT1_P8") (pintype "bidirectional"))
    )
    (net (code "61") (name "unconnected-(J2-DAT2-PadP1)") (class "Default")
      (node (ref "J2") (pin "P1") (pinfunction "DAT2_P1") (pintype "bidirectional"))
    )
    (net (code "62") (name "unconnected-(J2-DETECTION_1-PadS1)") (class "Default")
      (node (ref "J2") (pin "S1") (pinfunction "DETECTION_1_S1") (pintype "bidirectional"))
    )
    (net (code "63") (name "unconnected-(J2-DETECTION_2-PadS2)") (class "Default")
      (node (ref "J2") (pin "S2") (pinfunction "DETECTION_2_S2") (pintype "bidirectional"))
    )
    (net (code "64") (name "unconnected-(J3-Pad1)") (class "Default")
      (node (ref "J3") (pin "1") (pinfunction "1_1") (pintype "bidirectional"))
    )
    (net (code "65") (name "unconnected-(J3-Pad6)") (class "Default")
      (node (ref "J3") (pin "6") (pinfunction "6_6") (pintype "bidirectional"))
    )
    (net (code "66") (name "unconnected-(J3-Pad7)") (class "Default")
      (node (ref "J3") (pin "7") (pinfunction "7_7") (pintype "bidirectional"))
    )
    (net (code "67") (name "unconnected-(U2-NC-Pad22)") (class "Default")
      (node (ref "U2") (pin "22") (pinfunction "NC_22") (pintype "no_connect"))
    )
    (net (code "68") (name "unconnected-(U4-~{ALERT}-Pad5)") (class "Default")
      (node (ref "U4") (pin "5") (pinfunction "~{ALERT}_5") (pintype "output"))
    )
  )
)
